# sdcard.net
KiCad netlist of a schematic drawn in Altium Designer
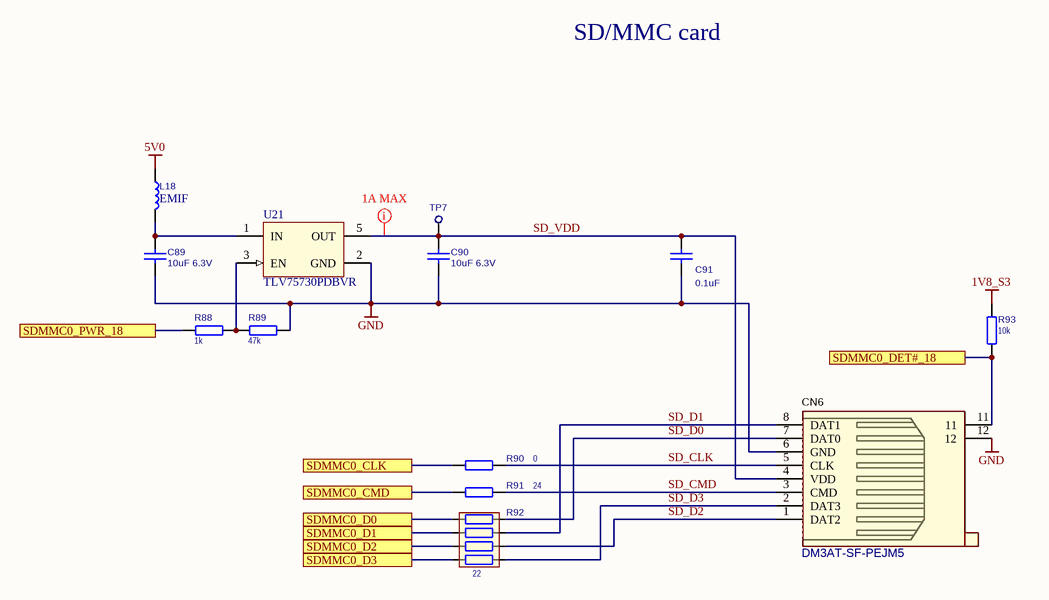
[diagram p0: sdcard.SchDoc]

(export (version "E")
  (design (tool "Eeschema 10.0.6"))
  (components
    (comp (ref "C89")
      (value "10uF 6.3V")
      (footprint "Capacitors:C0603")
      (description "CAP_NPOL")
      (fields (field (name "Comment") "CC0603MRX5R5BB106"))
      (libsource (lib "capacitors") (part "CAP_NPOL"))
    )
    (comp (ref "C90")
      (value "10uF 6.3V")
      (footprint "Capacitors:C0603")
      (description "CAP_NPOL")
      (fields (field (name "Comment") "CC0603MRX5R5BB106"))
      (libsource (lib "capacitors") (part "CAP_NPOL"))
    )
    (comp (ref "C91")
      (value "0.1uF")
      (footprint "Capacitors:C0603")
      (description "CAP_NPOL")
      (fields (field (name "Comment") "C1608X7R1H104K080AA"))
      (libsource (lib "capacitors") (part "CAP_NPOL"))
    )
    (comp (ref "CN6")
      (value "DM3AT-SF-PEJM5")
      (footprint "mSD_TF_push")
      (libsource (lib "uSD") (part "uSD card socket"))
    )
    (comp (ref "L18")
      (value "EMIF")
      (footprint "IND0603")
      (description "IND_WO_IRON")
      (fields (field (name "Comment") "BLM18AG102SN1D"))
      (libsource (lib "inductors") (part "IND_WO_IRON"))
    )
    (comp (ref "R88")
      (value "1k")
      (footprint "R0603")
      (description "RES")
      (libsource (lib "resistors") (part "RESISTOR"))
    )
    (comp (ref "R89")
      (value "47k")
      (footprint "R0603")
      (description "RES")
      (libsource (lib "resistors") (part "RESISTOR"))
    )
    (comp (ref "R90")
      (value "0")
      (footprint "R0603")
      (description "RES")
      (libsource (lib "resistors") (part "RESISTOR"))
    )
    (comp (ref "R91")
      (value "24")
      (footprint "R0603")
      (description "RES")
      (fields (field (name "Comment") "22"))
      (libsource (lib "resistors") (part "RESISTOR"))
    )
    (comp (ref "R92")
      (value "22")
      (footprint "Resistors:R0804X4")
      (description "ARRAY")
      (fields (field (name "Comment") "TC124-JR-0722RL"))
      (libsource (lib "resistors") (part "ARRAY"))
    )
    (comp (ref "R93")
      (value "10k")
      (footprint "R0603")
      (description "RES")
      (libsource (lib "resistors") (part "RESISTOR"))
    )
    (comp (ref "TP7")
      (value "TEST-POINT")
      (footprint "PAD")
      (description "PCB terminal block")
      (libsource (lib "TestPoint") (part "TEST-POINT"))
    )
    (comp (ref "U21")
      (value "TLV75730PDBVR")
      (footprint "SOT-23-5")
      (description "Capacitor-Free, 300-mA, Low-Dropout Regulator with Foldback Current Limit for Portable Devices")
      (libsource (lib "TLV733P") (part "TLV733P"))
    )
  )
  (nets
    (net (code "1") (name "/SDMMC0_CLK") (class "Default")
      (node (ref "R90") (pin "2") (pinfunction "2_2") (pintype "passive"))
    )
    (net (code "2") (name "/SDMMC0_CMD") (class "Default")
      (node (ref "R91") (pin "2") (pinfunction "2_2") (pintype "passive"))
    )
    (net (code "3") (name "/SDMMC0_D0") (class "Default")
      (node (ref "R92") (pin "1") (pinfunction "1_1") (pintype "passive"))
    )
    (net (code "4") (name "/SDMMC0_D1") (class "Default")
      (node (ref "R92") (pin "3") (pinfunction "3_3") (pintype "passive"))
    )
    (net (code "5") (name "/SDMMC0_D2") (class "Default")
      (node (ref "R92") (pin "5") (pinfunction "5_5") (pintype "passive"))
    )
    (net (code "6") (name "/SDMMC0_D3") (class "Default")
      (node (ref "R92") (pin "7") (pinfunction "7_7") (pintype "passive"))
    )
    (net (code "7") (name "/SDMMC0_DET#_18") (class "Default")
      (node (ref "CN6") (pin "11") (pinfunction "11_11") (pintype "passive"))
      (node (ref "R93") (pin "1") (pinfunction "1_1") (pintype "passive"))
    )
    (net (code "8") (name "/SDMMC0_PWR_18") (class "Default")
      (node (ref "R88") (pin "1") (pinfunction "1_1") (pintype "passive"))
    )
    (net (code "9") (name "/SD_CLK") (class "Default")
      (node (ref "CN6") (pin "5") (pinfunction "CLK_5") (pintype "passive"))
      (node (ref "R90") (pin "1") (pinfunction "1_1") (pintype "passive"))
    )
    (net (code "10") (name "/SD_CMD") (class "Default")
      (node (ref "CN6") (pin "3") (pinfunction "CMD_3") (pintype "passive"))
      (node (ref "R91") (pin "1") (pinfunction "1_1") (pintype "passive"))
    )
    (net (code "11") (name "/SD_D0") (class "Default")
      (node (ref "CN6") (pin "7") (pinfunction "DAT0_7") (pintype "passive"))
      (node (ref "R92") (pin "2") (pinfunction "2_2") (pintype "passive"))
    )
    (net (code "12") (name "/SD_D1") (class "Default")
      (node (ref "CN6") (pin "8") (pinfunction "DAT1_8") (pintype "passive"))
      (node (ref "R92") (pin "4") (pinfunction "4_4") (pintype "passive"))
    )
    (net (code "13") (name "/SD_D2") (class "Default")
      (node (ref "CN6") (pin "1") (pinfunction "DAT2_1") (pintype "passive"))
      (node (ref "R92") (pin "6") (pinfunction "6_6") (pintype "passive"))
    )
    (net (code "14") (name "/SD_D3") (class "Default")
      (node (ref "CN6") (pin "2") (pinfunction "DAT3_2") (pintype "passive"))
      (node (ref "R92") (pin "8") (pinfunction "8_8") (pintype "passive"))
    )
    (net (code "15") (name "/SD_VDD") (class "Default")
      (node (ref "C90") (pin "1") (pinfunction "1_1") (pintype "passive"))
      (node (ref "C91") (pin "2") (pinfunction "2_2") (pintype "passive"))
      (node (ref "CN6") (pin "4") (pinfunction "VDD_4") (pintype "passive"))
      (node (ref "TP7") (pin "1") (pinfunction "1_1") (pintype "passive"))
      (node (ref "U21") (pin "5") (pinfunction "OUT_5") (pintype "power_in"))
    )
    (net (code "16") (name "1V8_S3") (class "Default")
      (node (ref "R93") (pin "2") (pinfunction "2_2") (pintype "passive"))
    )
    (net (code "17") (name "5V0") (class "Default") (node (ref "L18") (pin "1") (pintype "passive")))
    (net (code "18") (name "GND") (class "Default")
      (node (ref "C89") (pin "2") (pinfunction "2_2") (pintype "passive"))
      (node (ref "C90") (pin "2") (pinfunction "2_2") (pintype "passive"))
      (node (ref "C91") (pin "1") (pinfunction "1_1") (pintype "passive"))
      (node (ref "CN6") (pin "12") (pinfunction "12_12") (pintype "passive"))
      (node (ref "CN6") (pin "6") (pinfunction "GND_6") (pintype "passive"))
      (node (ref "R89") (pin "2") (pinfunction "2_2") (pintype "passive"))
      (node (ref "U21") (pin "2") (pinfunction "GND_2") (pintype "power_in"))
    )
    (net (code "19") (name "Net-(U21-EN)") (class "Default")
      (node (ref "R88") (pin "2") (pinfunction "2_2") (pintype "passive"))
      (node (ref "R89") (pin "1") (pinfunction "1_1") (pintype "passive"))
      (node (ref "U21") (pin "3") (pinfunction "EN_3") (pintype "input"))
    )
    (net (code "20") (name "Net-(U21-IN)") (class "Default")
      (node (ref "C89") (pin "1") (pinfunction "1_1") (pintype "passive"))
      (node (ref "L18") (pin "2") (pintype "passive"))
      (node (ref "U21") (pin "1") (pinfunction "IN_1") (pintype "power_in"))
    )
  )
)
